# Screen_PCB.net
KiCad netlist of a schematic drawn in Altium Designer
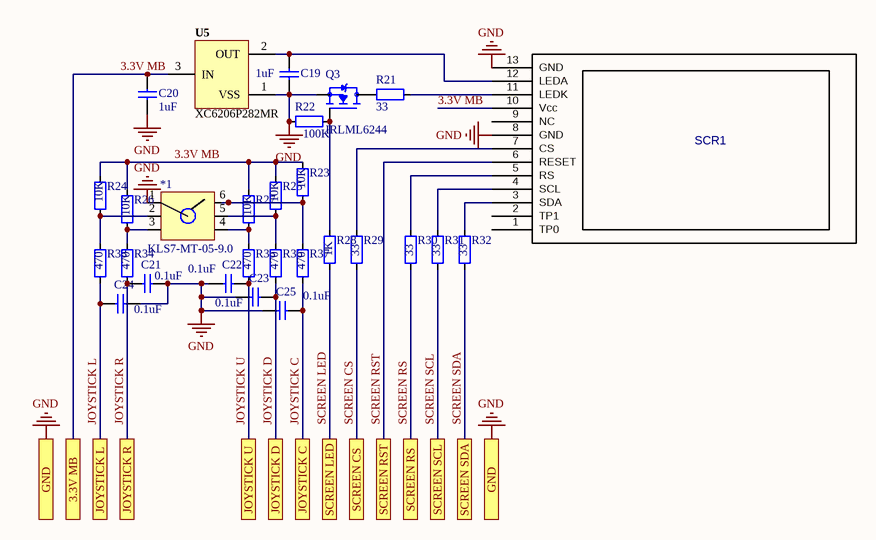
[diagram p0: Screen_PCB.SchDoc]

(export (version "E")
  (design (tool "Eeschema 10.0.6"))
  (components
    (comp (ref "*1")
      (value "KLS7-MT-05-9.0")
      (footprint "KLS7-MT-05-9.0")
      (libsource (lib "V_NB-IoT_3.1") (part "KLS7-MT-05-9.0"))
    )
    (comp (ref "C19") (value "1uF") (footprint "C0805") (libsource (lib "V_NB-IoT_3.1") (part "CAP")))
    (comp (ref "C20") (value "1uF") (footprint "C0805") (libsource (lib "V_NB-IoT_3.1") (part "CAP")))
    (comp (ref "C21") (value "0.1uF") (footprint "R0603") (libsource (lib "V_NB-IoT_3.1") (part "CAP")))
    (comp (ref "C22") (value "0.1uF") (footprint "R0603") (libsource (lib "V_NB-IoT_3.1") (part "CAP")))
    (comp (ref "C23") (value "0.1uF") (footprint "R0603") (libsource (lib "V_NB-IoT_3.1") (part "CAP")))
    (comp (ref "C24") (value "0.1uF") (footprint "R0603") (libsource (lib "V_NB-IoT_3.1") (part "CAP")))
    (comp (ref "C25") (value "0.1uF") (footprint "R0603") (libsource (lib "V_NB-IoT_3.1") (part "CAP")))
    (comp (ref "Q3")
      (value "IRLML6244")
      (footprint "SOT95P237X112-3N")
      (description "MOSFET P-CH 30V 3.6A SOT-23-3")
      (fields
        (field (name "MF") "{'manufacturer': u'Infineon Technologies'}")
        (field (name "MP") "IRLML9301TRPBF")
      )
      (libsource (lib "V_NB-IoT_3.1") (part "IRLML6244"))
    )
    (comp (ref "R21")
      (value "33")
      (footprint "R0603")
      (description "Resistor SMD")
      (libsource (lib "V_NB-IoT_3.1") (part "RES SMD UNI"))
    )
    (comp (ref "R22")
      (value "100K")
      (footprint "R0603")
      (description "Resistor SMD")
      (libsource (lib "V_NB-IoT_3.1") (part "RES SMD UNI"))
    )
    (comp (ref "R23")
      (value "10K")
      (footprint "R0603")
      (description "Resistor SMD")
      (libsource (lib "V_NB-IoT_3.1") (part "RES SMD UNI"))
    )
    (comp (ref "R24")
      (value "10K")
      (footprint "R0603")
      (description "Resistor SMD")
      (libsource (lib "V_NB-IoT_3.1") (part "RES SMD UNI"))
    )
    (comp (ref "R25")
      (value "10K")
      (footprint "R0603")
      (description "Resistor SMD")
      (libsource (lib "V_NB-IoT_3.1") (part "RES SMD UNI"))
    )
    (comp (ref "R26")
      (value "10K")
      (footprint "R0603")
      (description "Resistor SMD")
      (libsource (lib "V_NB-IoT_3.1") (part "RES SMD UNI"))
    )
    (comp (ref "R27")
      (value "10K")
      (footprint "R0603")
      (description "Resistor SMD")
      (libsource (lib "V_NB-IoT_3.1") (part "RES SMD UNI"))
    )
    (comp (ref "R28")
      (value "1K")
      (footprint "R0603")
      (description "Resistor SMD")
      (libsource (lib "V_NB-IoT_3.1") (part "RES SMD UNI"))
    )
    (comp (ref "R29")
      (value "33")
      (footprint "R0603")
      (description "Resistor SMD")
      (libsource (lib "V_NB-IoT_3.1") (part "RES SMD UNI"))
    )
    (comp (ref "R30")
      (value "33")
      (footprint "R0603")
      (description "Resistor SMD")
      (libsource (lib "V_NB-IoT_3.1") (part "RES SMD UNI"))
    )
    (comp (ref "R31")
      (value "33")
      (footprint "R0603")
      (description "Resistor SMD")
      (libsource (lib "V_NB-IoT_3.1") (part "RES SMD UNI"))
    )
    (comp (ref "R32")
      (value "33")
      (footprint "R0603")
      (description "Resistor SMD")
      (libsource (lib "V_NB-IoT_3.1") (part "RES SMD UNI"))
    )
    (comp (ref "R33")
      (value "470")
      (footprint "R0603")
      (description "Resistor SMD")
      (libsource (lib "V_NB-IoT_3.1") (part "RES SMD UNI"))
    )
    (comp (ref "R34")
      (value "470")
      (footprint "R0603")
      (description "Resistor SMD")
      (libsource (lib "V_NB-IoT_3.1") (part "RES SMD UNI"))
    )
    (comp (ref "R35")
      (value "470")
      (footprint "R0603")
      (description "Resistor SMD")
      (libsource (lib "V_NB-IoT_3.1") (part "RES SMD UNI"))
    )
    (comp (ref "R36")
      (value "470")
      (footprint "R0603")
      (description "Resistor SMD")
      (libsource (lib "V_NB-IoT_3.1") (part "RES SMD UNI"))
    )
    (comp (ref "R37")
      (value "470")
      (footprint "R0603")
      (description "Resistor SMD")
      (libsource (lib "V_NB-IoT_3.1") (part "RES SMD UNI"))
    )
    (comp (ref "SCR1")
      (value "0.96INCH_TFT")
      (footprint "0.96INCH_TFT")
      (description "LH096T-IG01 TFT RGB 0,96\" screen")
      (libsource (lib "V_NB-IoT_3.1") (part "0.96INCH_TFT"))
    )
    (comp (ref "U5")
      (value "XC6206P282MR")
      (footprint "SOT95P237X112-3N")
      (fields (field (name "MANUFACTURER") "UTD"))
      (libsource (lib "V_NB-IoT_3.1") (part "XC6206P282MR"))
    )
  )
  (nets
    (net (code "1") (name "/3.3V MB") (class "Default")
      (node (ref "C20") (pin "2") (pinfunction "2_2") (pintype "passive"))
      (node (ref "R23") (pin "1") (pinfunction "1_1") (pintype "passive"))
      (node (ref "R24") (pin "1") (pinfunction "1_1") (pintype "passive"))
      (node (ref "R25") (pin "1") (pinfunction "1_1") (pintype "passive"))
      (node (ref "R26") (pin "1") (pinfunction "1_1") (pintype "passive"))
      (node (ref "R27") (pin "1") (pinfunction "1_1") (pintype "passive"))
      (node (ref "SCR1") (pin "10") (pinfunction "Vcc_10") (pintype "passive"))
      (node (ref "U5") (pin "3") (pinfunction "IN_3") (pintype "passive"))
    )
    (net (code "2") (name "/JOYSTICK C") (class "Default")
      (node (ref "C25") (pin "1") (pinfunction "1_1") (pintype "passive"))
      (node (ref "R37") (pin "2") (pinfunction "2_2") (pintype "passive"))
    )
    (net (code "3") (name "/JOYSTICK D") (class "Default")
      (node (ref "C23") (pin "1") (pinfunction "1_1") (pintype "passive"))
      (node (ref "R36") (pin "2") (pinfunction "2_2") (pintype "passive"))
    )
    (net (code "4") (name "/JOYSTICK L") (class "Default")
      (node (ref "C24") (pin "2") (pinfunction "2_2") (pintype "passive"))
      (node (ref "R33") (pin "2") (pinfunction "2_2") (pintype "passive"))
    )
    (net (code "5") (name "/JOYSTICK R") (class "Default")
      (node (ref "C21") (pin "2") (pinfunction "2_2") (pintype "passive"))
      (node (ref "R34") (pin "2") (pinfunction "2_2") (pintype "passive"))
    )
    (net (code "6") (name "/JOYSTICK U") (class "Default")
      (node (ref "C22") (pin "1") (pinfunction "1_1") (pintype "passive"))
      (node (ref "R35") (pin "2") (pinfunction "2_2") (pintype "passive"))
    )
    (net (code "7") (name "/SCREEN CS") (class "Default")
      (node (ref "R29") (pin "2") (pinfunction "2_2") (pintype "passive"))
    )
    (net (code "8") (name "/SCREEN LED") (class "Default")
      (node (ref "R28") (pin "2") (pinfunction "2_2") (pintype "passive"))
    )
    (net (code "9") (name "/SCREEN RS") (class "Default")
      (node (ref "R30") (pin "2") (pinfunction "2_2") (pintype "passive"))
    )
    (net (code "10") (name "/SCREEN RST") (class "Default")
      (node (ref "SCR1") (pin "6") (pinfunction "RESET_6") (pintype "passive"))
    )
    (net (code "11") (name "/SCREEN SCL") (class "Default")
      (node (ref "R31") (pin "2") (pinfunction "2_2") (pintype "passive"))
    )
    (net (code "12") (name "/SCREEN SDA") (class "Default")
      (node (ref "R32") (pin "2") (pinfunction "2_2") (pintype "passive"))
    )
    (net (code "13") (name "GND") (class "Default")
      (node (ref "*1") (pin "1") (pintype "passive"))
      (node (ref "C19") (pin "1") (pinfunction "1_1") (pintype "passive"))
      (node (ref "C20") (pin "1") (pinfunction "1_1") (pintype "passive"))
      (node (ref "C21") (pin "1") (pinfunction "1_1") (pintype "passive"))
      (node (ref "C22") (pin "2") (pinfunction "2_2") (pintype "passive"))
      (node (ref "C23") (pin "2") (pinfunction "2_2") (pintype "passive"))
      (node (ref "C24") (pin "1") (pinfunction "1_1") (pintype "passive"))
      (node (ref "C25") (pin "2") (pinfunction "2_2") (pintype "passive"))
      (node (ref "Q3") (pin "2") (pinfunction "S_2") (pintype "passive"))
      (node (ref "R22") (pin "1") (pinfunction "1_1") (pintype "passive"))
      (node (ref "SCR1") (pin "13") (pinfunction "GND_13") (pintype "passive"))
      (node (ref "SCR1") (pin "8") (pinfunction "GND_8") (pintype "passive"))
      (node (ref "U5") (pin "1") (pinfunction "VSS_1") (pintype "passive"))
    )
    (net (code "14") (name "Net-(*1-Pad2)") (class "Default")
      (node (ref "*1") (pin "2") (pintype "passive"))
      (node (ref "R24") (pin "2") (pinfunction "2_2") (pintype "passive"))
      (node (ref "R33") (pin "1") (pinfunction "1_1") (pintype "passive"))
    )
    (net (code "15") (name "Net-(*1-Pad3)") (class "Default")
      (node (ref "*1") (pin "3") (pintype "passive"))
      (node (ref "R26") (pin "2") (pinfunction "2_2") (pintype "passive"))
      (node (ref "R34") (pin "1") (pinfunction "1_1") (pintype "passive"))
    )
    (net (code "16") (name "Net-(*1-Pad4)") (class "Default")
      (node (ref "*1") (pin "4") (pintype "passive"))
      (node (ref "R27") (pin "2") (pinfunction "2_2") (pintype "passive"))
      (node (ref "R35") (pin "1") (pinfunction "1_1") (pintype "passive"))
    )
    (net (code "17") (name "Net-(*1-Pad5)") (class "Default")
      (node (ref "*1") (pin "5") (pintype "passive"))
      (node (ref "R25") (pin "2") (pinfunction "2_2") (pintype "passive"))
      (node (ref "R36") (pin "1") (pinfunction "1_1") (pintype "passive"))
    )
    (net (code "18") (name "Net-(*1-Pad6)") (class "Default")
      (node (ref "*1") (pin "6") (pintype "passive"))
      (node (ref "R23") (pin "2") (pinfunction "2_2") (pintype "passive"))
      (node (ref "R37") (pin "1") (pinfunction "1_1") (pintype "passive"))
    )
    (net (code "19") (name "Net-(Q3-D)") (class "Default")
      (node (ref "Q3") (pin "3") (pinfunction "D_3") (pintype "passive"))
      (node (ref "R21") (pin "2") (pinfunction "2_2") (pintype "passive"))
    )
    (net (code "20") (name "Net-(Q3-G)") (class "Default")
      (node (ref "Q3") (pin "1") (pinfunction "G_1") (pintype "passive"))
      (node (ref "R22") (pin "2") (pinfunction "2_2") (pintype "passive"))
      (node (ref "R28") (pin "1") (pinfunction "1_1") (pintype "passive"))
    )
    (net (code "21") (name "Net-(SCR1-CS)") (class "Default")
      (node (ref "R29") (pin "1") (pinfunction "1_1") (pintype "passive"))
      (node (ref "SCR1") (pin "7") (pinfunction "CS_7") (pintype "passive"))
    )
    (net (code "22") (name "Net-(SCR1-LEDA)") (class "Default")
      (node (ref "C19") (pin "2") (pinfunction "2_2") (pintype "passive"))
      (node (ref "SCR1") (pin "12") (pinfunction "LEDA_12") (pintype "passive"))
      (node (ref "U5") (pin "2") (pinfunction "OUT_2") (pintype "power_in"))
    )
    (net (code "23") (name "Net-(SCR1-LEDK)") (class "Default")
      (node (ref "R21") (pin "1") (pinfunction "1_1") (pintype "passive"))
      (node (ref "SCR1") (pin "11") (pinfunction "LEDK_11") (pintype "passive"))
    )
    (net (code "24") (name "Net-(SCR1-RS)") (class "Default")
      (node (ref "R30") (pin "1") (pinfunction "1_1") (pintype "passive"))
      (node (ref "SCR1") (pin "5") (pinfunction "RS_5") (pintype "passive"))
    )
    (net (code "25") (name "Net-(SCR1-SCL)") (class "Default")
      (node (ref "R31") (pin "1") (pinfunction "1_1") (pintype "passive"))
      (node (ref "SCR1") (pin "4") (pinfunction "SCL_4") (pintype "passive"))
    )
    (net (code "26") (name "Net-(SCR1-SDA)") (class "Default")
      (node (ref "R32") (pin "1") (pinfunction "1_1") (pintype "passive"))
      (node (ref "SCR1") (pin "3") (pinfunction "SDA_3") (pintype "passive"))
    )
    (net (code "27") (name "unconnected-(SCR1-NC-Pad9)") (class "Default")
      (node (ref "SCR1") (pin "9") (pinfunction "NC_9") (pintype "passive"))
    )
    (net (code "28") (name "unconnected-(SCR1-TP0-Pad1)") (class "Default")
      (node (ref "SCR1") (pin "1") (pinfunction "TP0_1") (pintype "passive"))
    )
    (net (code "29") (name "unconnected-(SCR1-TP1-Pad2)") (class "Default")
      (node (ref "SCR1") (pin "2") (pinfunction "TP1_2") (pintype "passive"))
    )
  )
)
